# SCH_Final_Syntheseproject_Oliver_2023-12.net
KiCad netlist of a schematic drawn in EasyEDA
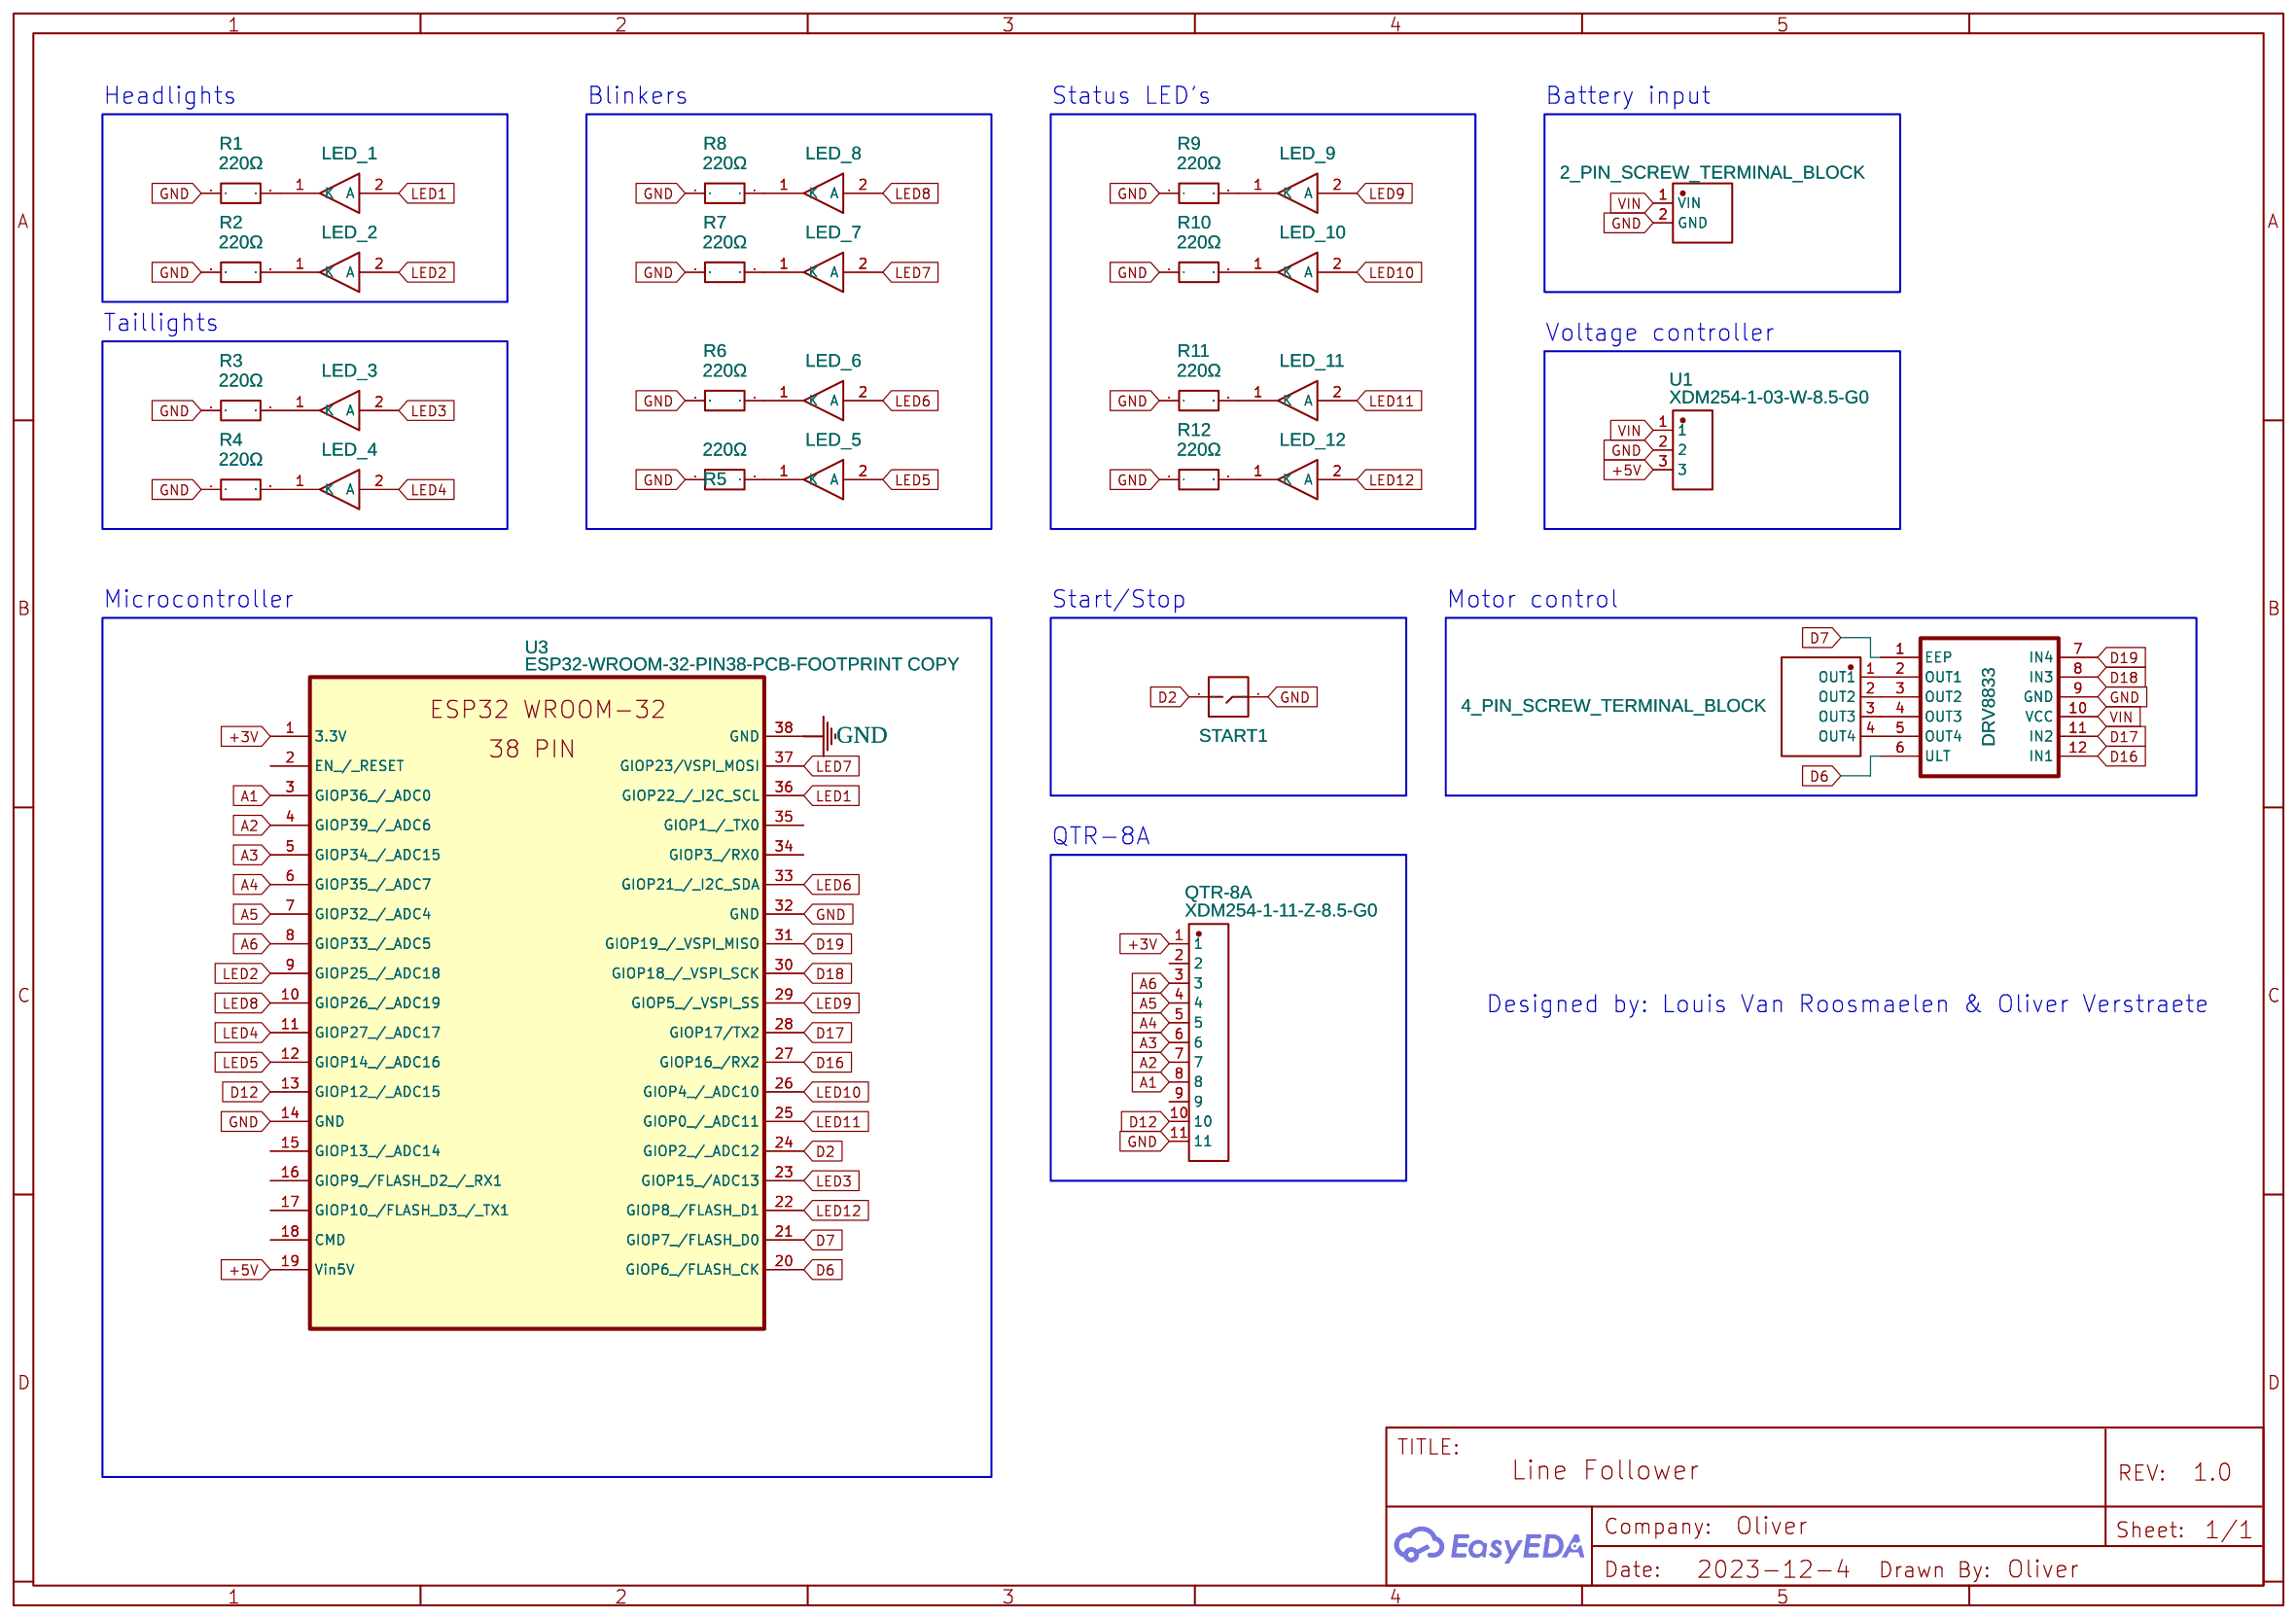
[diagram p0: schematic sheet]

(export (version "E")
  (design (tool "Eeschema 10.0.6"))
  (components
    (comp (ref "2_PIN_SCREW_TERMINAL_BLOCK")
      (value "2 Pin Screw Terminal Block Connector 2.54 mm")
      (libsource (lib "") (part "2 PIN SCREW TERMINAL BLOCK CONNECTOR 2.54 MM"))
    )
    (comp (ref "4_PIN_SCREW_TERMINAL_BLOCK")
      (value "4 PIN SCREW TERMINAL BLOCK CONNECTOR 2.54 MM")
      (libsource (lib "") (part "4 PIN SCREW TERMINAL BLOCK CONNECTOR 2.54 MM"))
    )
    (comp (ref "DRV8833") (value "DRV8833") (libsource (lib "") (part "DRV8833 12PIN")))
    (comp (ref "LED_1") (value "led 5 mm") (libsource (lib "") (part "led 5 mm")))
    (comp (ref "LED_2") (value "led 5 mm") (libsource (lib "") (part "led 5 mm")))
    (comp (ref "LED_3") (value "led 5 mm") (libsource (lib "") (part "led 5 mm")))
    (comp (ref "LED_4") (value "led 5 mm") (libsource (lib "") (part "led 5 mm")))
    (comp (ref "LED_5") (value "led 5 mm") (libsource (lib "") (part "led 5 mm")))
    (comp (ref "LED_6") (value "led 5 mm") (libsource (lib "") (part "led 5 mm")))
    (comp (ref "LED_7") (value "led 5 mm") (libsource (lib "") (part "led 5 mm")))
    (comp (ref "LED_8") (value "led 5 mm") (libsource (lib "") (part "led 5 mm")))
    (comp (ref "LED_9") (value "led 5 mm") (libsource (lib "") (part "led 5 mm")))
    (comp (ref "LED_10") (value "led 5 mm") (libsource (lib "") (part "led 5 mm")))
    (comp (ref "LED_11") (value "led 5 mm") (libsource (lib "") (part "led 5 mm")))
    (comp (ref "LED_12") (value "led 5 mm") (libsource (lib "") (part "led 5 mm")))
    (comp (ref "QTR-8A")
      (value "XDM254-1-11-Z-8.5-G0")
      (fields (field (name "Manufacturer") "XUNDA(讯答)"))
      (libsource (lib "") (part "XDM254-1-11-Z-8.5-G0"))
    )
    (comp (ref "R1")
      (value "220Ω")
      (libsource (lib "") (part "AXIAL RESISTOR 220 OHM - TH_BD2.3-L6.0-P10.00-D0.4"))
    )
    (comp (ref "R2")
      (value "220Ω")
      (libsource (lib "") (part "AXIAL RESISTOR 220 OHM - TH_BD2.3-L6.0-P10.00-D0.4"))
    )
    (comp (ref "R3")
      (value "220Ω")
      (libsource (lib "") (part "AXIAL RESISTOR 220 OHM - TH_BD2.3-L6.0-P10.00-D0.4"))
    )
    (comp (ref "R4")
      (value "220Ω")
      (libsource (lib "") (part "AXIAL RESISTOR 220 OHM - TH_BD2.3-L6.0-P10.00-D0.4"))
    )
    (comp (ref "R5")
      (value "220Ω")
      (libsource (lib "") (part "AXIAL RESISTOR 220 OHM - TH_BD2.3-L6.0-P10.00-D0.4"))
    )
    (comp (ref "R6")
      (value "220Ω")
      (libsource (lib "") (part "AXIAL RESISTOR 220 OHM - TH_BD2.3-L6.0-P10.00-D0.4"))
    )
    (comp (ref "R7")
      (value "220Ω")
      (libsource (lib "") (part "AXIAL RESISTOR 220 OHM - TH_BD2.3-L6.0-P10.00-D0.4"))
    )
    (comp (ref "R8")
      (value "220Ω")
      (libsource (lib "") (part "AXIAL RESISTOR 220 OHM - TH_BD2.3-L6.0-P10.00-D0.4"))
    )
    (comp (ref "R9")
      (value "220Ω")
      (libsource (lib "") (part "AXIAL RESISTOR 220 OHM - TH_BD2.3-L6.0-P10.00-D0.4"))
    )
    (comp (ref "R10")
      (value "220Ω")
      (libsource (lib "") (part "AXIAL RESISTOR 220 OHM - TH_BD2.3-L6.0-P10.00-D0.4"))
    )
    (comp (ref "R11")
      (value "220Ω")
      (libsource (lib "") (part "AXIAL RESISTOR 220 OHM - TH_BD2.3-L6.0-P10.00-D0.4"))
    )
    (comp (ref "R12")
      (value "220Ω")
      (libsource (lib "") (part "AXIAL RESISTOR 220 OHM - TH_BD2.3-L6.0-P10.00-D0.4"))
    )
    (comp (ref "START1") (value "start") (libsource (lib "") (part "Push Button")))
    (comp (ref "U1")
      (value "XDM254-1-03-W-8.5-G0")
      (fields (field (name "Manufacturer") "XUNDA(讯答)"))
      (libsource (lib "") (part "XDM254-1-03-W-8.5-G0"))
    )
    (comp (ref "U3")
      (value "ESP32-WROOM-32-PIN38-PCB-FOOTPRINT COPY")
      (fields
        (field (name "Manufacturer Part") "ESP32-WROOM-32")
        (field (name "Manufacturer") "Espressif Systems")
      )
      (libsource (lib "") (part "ESP32-WROOM-32-PIN38-PCB-FOOTPRINT COPY"))
    )
  )
  (nets
    (net (code "1") (name "+3V") (class "Default")
      (node (ref "QTR-8A") (pin "1") (pinfunction "1_1") (pintype "unspecified"))
      (node (ref "U3") (pin "1") (pinfunction "3.3V_1") (pintype "unspecified"))
    )
    (net (code "2") (name "+5V") (class "Default")
      (node (ref "U1") (pin "3") (pinfunction "3_3") (pintype "unspecified"))
      (node (ref "U3") (pin "19") (pinfunction "Vin5V_19") (pintype "unspecified"))
    )
    (net (code "3") (name "A1") (class "Default")
      (node (ref "QTR-8A") (pin "8") (pinfunction "8_8") (pintype "unspecified"))
      (node (ref "U3") (pin "3") (pinfunction "GIOP36_/_ADC0_3") (pintype "unspecified"))
    )
    (net (code "4") (name "A2") (class "Default")
      (node (ref "QTR-8A") (pin "7") (pinfunction "7_7") (pintype "unspecified"))
      (node (ref "U3") (pin "4") (pinfunction "GIOP39_/_ADC6_4") (pintype "unspecified"))
    )
    (net (code "5") (name "A3") (class "Default")
      (node (ref "QTR-8A") (pin "6") (pinfunction "6_6") (pintype "unspecified"))
      (node (ref "U3") (pin "5") (pinfunction "GIOP34_/_ADC15_5") (pintype "unspecified"))
    )
    (net (code "6") (name "A4") (class "Default")
      (node (ref "QTR-8A") (pin "5") (pinfunction "5_5") (pintype "unspecified"))
      (node (ref "U3") (pin "6") (pinfunction "GIOP35_/_ADC7_6") (pintype "unspecified"))
    )
    (net (code "7") (name "A5") (class "Default")
      (node (ref "QTR-8A") (pin "4") (pinfunction "4_4") (pintype "unspecified"))
      (node (ref "U3") (pin "7") (pinfunction "GIOP32_/_ADC4_7") (pintype "unspecified"))
    )
    (net (code "8") (name "A6") (class "Default")
      (node (ref "QTR-8A") (pin "3") (pinfunction "3_3") (pintype "unspecified"))
      (node (ref "U3") (pin "8") (pinfunction "GIOP33_/_ADC5_8") (pintype "unspecified"))
    )
    (net (code "9") (name "D2") (class "Default")
      (node (ref "START1") (pin "1") (pinfunction "1_1") (pintype "unspecified"))
      (node (ref "U3") (pin "24") (pinfunction "GIOP2_/_ADC12_24") (pintype "unspecified"))
    )
    (net (code "10") (name "D6") (class "Default")
      (node (ref "DRV8833") (pin "6") (pinfunction "ULT_6") (pintype "unspecified"))
      (node (ref "U3") (pin "20") (pinfunction "GIOP6_/FLASH_CK_20") (pintype "unspecified"))
    )
    (net (code "11") (name "D7") (class "Default")
      (node (ref "DRV8833") (pin "1") (pinfunction "EEP_1") (pintype "unspecified"))
      (node (ref "U3") (pin "21") (pinfunction "GIOP7_/FLASH_D0_21") (pintype "unspecified"))
    )
    (net (code "12") (name "D12") (class "Default")
      (node (ref "QTR-8A") (pin "10") (pinfunction "10_10") (pintype "unspecified"))
      (node (ref "U3") (pin "13") (pinfunction "GIOP12_/_ADC15_13") (pintype "unspecified"))
    )
    (net (code "13") (name "D16") (class "Default")
      (node (ref "DRV8833") (pin "12") (pinfunction "IN1_12") (pintype "unspecified"))
      (node (ref "U3") (pin "27") (pinfunction "GIOP16_/RX2_27") (pintype "unspecified"))
    )
    (net (code "14") (name "D17") (class "Default")
      (node (ref "DRV8833") (pin "11") (pinfunction "IN2_11") (pintype "unspecified"))
      (node (ref "U3") (pin "28") (pinfunction "GIOP17/TX2_28") (pintype "unspecified"))
    )
    (net (code "15") (name "D18") (class "Default")
      (node (ref "DRV8833") (pin "8") (pinfunction "IN3_8") (pintype "unspecified"))
      (node (ref "U3") (pin "30") (pinfunction "GIOP18_/_VSPI_SCK_30") (pintype "unspecified"))
    )
    (net (code "16") (name "D19") (class "Default")
      (node (ref "DRV8833") (pin "7") (pinfunction "IN4_7") (pintype "unspecified"))
      (node (ref "U3") (pin "31") (pinfunction "GIOP19_/_VSPI_MISO_31") (pintype "unspecified"))
    )
    (net (code "17") (name "GND") (class "Default")
      (node (ref "2_PIN_SCREW_TERMINAL_BLOCK") (pin "2") (pinfunction "GND_2") (pintype "unspecified"))
      (node (ref "DRV8833") (pin "9") (pinfunction "GND_9") (pintype "unspecified"))
      (node (ref "QTR-8A") (pin "11") (pinfunction "11_11") (pintype "unspecified"))
      (node (ref "R1") (pin "1") (pinfunction "1_1") (pintype "unspecified"))
      (node (ref "R10") (pin "1") (pinfunction "1_1") (pintype "unspecified"))
      (node (ref "R11") (pin "1") (pinfunction "1_1") (pintype "unspecified"))
      (node (ref "R12") (pin "1") (pinfunction "1_1") (pintype "unspecified"))
      (node (ref "R2") (pin "1") (pinfunction "1_1") (pintype "unspecified"))
      (node (ref "R3") (pin "1") (pinfunction "1_1") (pintype "unspecified"))
      (node (ref "R4") (pin "1") (pinfunction "1_1") (pintype "unspecified"))
      (node (ref "R5") (pin "1") (pinfunction "1_1") (pintype "unspecified"))
      (node (ref "R6") (pin "1") (pinfunction "1_1") (pintype "unspecified"))
      (node (ref "R7") (pin "1") (pinfunction "1_1") (pintype "unspecified"))
      (node (ref "R8") (pin "1") (pinfunction "1_1") (pintype "unspecified"))
      (node (ref "R9") (pin "1") (pinfunction "1_1") (pintype "unspecified"))
      (node (ref "START1") (pin "2") (pinfunction "2_2") (pintype "unspecified"))
      (node (ref "U1") (pin "2") (pinfunction "2_2") (pintype "unspecified"))
      (node (ref "U3") (pin "14") (pinfunction "GND_14") (pintype "unspecified"))
      (node (ref "U3") (pin "32") (pinfunction "GND_32") (pintype "unspecified"))
      (node (ref "U3") (pin "38") (pinfunction "GND_38") (pintype "unspecified"))
    )
    (net (code "18") (name "LED1") (class "Default")
      (node (ref "LED_1") (pin "2") (pinfunction "A_2") (pintype "unspecified"))
      (node (ref "U3") (pin "36") (pinfunction "GIOP22_/_I2C_SCL_36") (pintype "unspecified"))
    )
    (net (code "19") (name "LED2") (class "Default")
      (node (ref "LED_2") (pin "2") (pinfunction "A_2") (pintype "unspecified"))
      (node (ref "U3") (pin "9") (pinfunction "GIOP25_/_ADC18_9") (pintype "unspecified"))
    )
    (net (code "20") (name "LED3") (class "Default")
      (node (ref "LED_3") (pin "2") (pinfunction "A_2") (pintype "unspecified"))
      (node (ref "U3") (pin "23") (pinfunction "GIOP15_/ADC13_23") (pintype "unspecified"))
    )
    (net (code "21") (name "LED4") (class "Default")
      (node (ref "LED_4") (pin "2") (pinfunction "A_2") (pintype "unspecified"))
      (node (ref "U3") (pin "11") (pinfunction "GIOP27_/_ADC17_11") (pintype "unspecified"))
    )
    (net (code "22") (name "LED5") (class "Default")
      (node (ref "LED_5") (pin "2") (pinfunction "A_2") (pintype "unspecified"))
      (node (ref "U3") (pin "12") (pinfunction "GIOP14_/_ADC16_12") (pintype "unspecified"))
    )
    (net (code "23") (name "LED6") (class "Default")
      (node (ref "LED_6") (pin "2") (pinfunction "A_2") (pintype "unspecified"))
      (node (ref "U3") (pin "33") (pinfunction "GIOP21_/_I2C_SDA_33") (pintype "unspecified"))
    )
    (net (code "24") (name "LED7") (class "Default")
      (node (ref "LED_7") (pin "2") (pinfunction "A_2") (pintype "unspecified"))
      (node (ref "U3") (pin "37") (pinfunction "GIOP23/VSPI_MOSI_37") (pintype "unspecified"))
    )
    (net (code "25") (name "LED8") (class "Default")
      (node (ref "LED_8") (pin "2") (pinfunction "A_2") (pintype "unspecified"))
      (node (ref "U3") (pin "10") (pinfunction "GIOP26_/_ADC19_10") (pintype "unspecified"))
    )
    (net (code "26") (name "LED9") (class "Default")
      (node (ref "LED_9") (pin "2") (pinfunction "A_2") (pintype "unspecified"))
      (node (ref "U3") (pin "29") (pinfunction "GIOP5_/_VSPI_SS_29") (pintype "unspecified"))
    )
    (net (code "27") (name "LED10") (class "Default")
      (node (ref "LED_10") (pin "2") (pinfunction "A_2") (pintype "unspecified"))
      (node (ref "U3") (pin "26") (pinfunction "GIOP4_/_ADC10_26") (pintype "unspecified"))
    )
    (net (code "28") (name "LED11") (class "Default")
      (node (ref "LED_11") (pin "2") (pinfunction "A_2") (pintype "unspecified"))
      (node (ref "U3") (pin "25") (pinfunction "GIOP0_/_ADC11_25") (pintype "unspecified"))
    )
    (net (code "29") (name "LED12") (class "Default")
      (node (ref "LED_12") (pin "2") (pinfunction "A_2") (pintype "unspecified"))
      (node (ref "U3") (pin "22") (pinfunction "GIOP8_/FLASH_D1_22") (pintype "unspecified"))
    )
    (net (code "30") (name "Net-(4_PIN_SCREW_TERMINAL_BLOCK-OUT1)") (class "Default")
      (node (ref "4_PIN_SCREW_TERMINAL_BLOCK") (pin "1") (pinfunction "OUT1_1") (pintype "unspecified"))
      (node (ref "DRV8833") (pin "2") (pinfunction "OUT1_2") (pintype "unspecified"))
    )
    (net (code "31") (name "Net-(4_PIN_SCREW_TERMINAL_BLOCK-OUT2)") (class "Default")
      (node (ref "4_PIN_SCREW_TERMINAL_BLOCK") (pin "2") (pinfunction "OUT2_2") (pintype "unspecified"))
      (node (ref "DRV8833") (pin "3") (pinfunction "OUT2_3") (pintype "unspecified"))
    )
    (net (code "32") (name "Net-(4_PIN_SCREW_TERMINAL_BLOCK-OUT3)") (class "Default")
      (node (ref "4_PIN_SCREW_TERMINAL_BLOCK") (pin "3") (pinfunction "OUT3_3") (pintype "unspecified"))
      (node (ref "DRV8833") (pin "4") (pinfunction "OUT3_4") (pintype "unspecified"))
    )
    (net (code "33") (name "Net-(4_PIN_SCREW_TERMINAL_BLOCK-OUT4)") (class "Default")
      (node (ref "4_PIN_SCREW_TERMINAL_BLOCK") (pin "4") (pinfunction "OUT4_4") (pintype "unspecified"))
      (node (ref "DRV8833") (pin "5") (pinfunction "OUT4_5") (pintype "unspecified"))
    )
    (net (code "34") (name "Net-(LED_1-K)") (class "Default")
      (node (ref "LED_1") (pin "1") (pinfunction "K_1") (pintype "unspecified"))
      (node (ref "R1") (pin "2") (pinfunction "2_2") (pintype "unspecified"))
    )
    (net (code "35") (name "Net-(LED_2-K)") (class "Default")
      (node (ref "LED_2") (pin "1") (pinfunction "K_1") (pintype "unspecified"))
      (node (ref "R2") (pin "2") (pinfunction "2_2") (pintype "unspecified"))
    )
    (net (code "36") (name "Net-(LED_3-K)") (class "Default")
      (node (ref "LED_3") (pin "1") (pinfunction "K_1") (pintype "unspecified"))
      (node (ref "R3") (pin "2") (pinfunction "2_2") (pintype "unspecified"))
    )
    (net (code "37") (name "Net-(LED_4-K)") (class "Default")
      (node (ref "LED_4") (pin "1") (pinfunction "K_1") (pintype "unspecified"))
      (node (ref "R4") (pin "2") (pinfunction "2_2") (pintype "unspecified"))
    )
    (net (code "38") (name "Net-(LED_5-K)") (class "Default")
      (node (ref "LED_5") (pin "1") (pinfunction "K_1") (pintype "unspecified"))
      (node (ref "R5") (pin "2") (pinfunction "2_2") (pintype "unspecified"))
    )
    (net (code "39") (name "Net-(LED_6-K)") (class "Default")
      (node (ref "LED_6") (pin "1") (pinfunction "K_1") (pintype "unspecified"))
      (node (ref "R6") (pin "2") (pinfunction "2_2") (pintype "unspecified"))
    )
    (net (code "40") (name "Net-(LED_7-K)") (class "Default")
      (node (ref "LED_7") (pin "1") (pinfunction "K_1") (pintype "unspecified"))
      (node (ref "R7") (pin "2") (pinfunction "2_2") (pintype "unspecified"))
    )
    (net (code "41") (name "Net-(LED_8-K)") (class "Default")
      (node (ref "LED_8") (pin "1") (pinfunction "K_1") (pintype "unspecified"))
      (node (ref "R8") (pin "2") (pinfunction "2_2") (pintype "unspecified"))
    )
    (net (code "42") (name "Net-(LED_9-K)") (class "Default")
      (node (ref "LED_9") (pin "1") (pinfunction "K_1") (pintype "unspecified"))
      (node (ref "R9") (pin "2") (pinfunction "2_2") (pintype "unspecified"))
    )
    (net (code "43") (name "Net-(LED_10-K)") (class "Default")
      (node (ref "LED_10") (pin "1") (pinfunction "K_1") (pintype "unspecified"))
      (node (ref "R10") (pin "2") (pinfunction "2_2") (pintype "unspecified"))
    )
    (net (code "44") (name "Net-(LED_11-K)") (class "Default")
      (node (ref "LED_11") (pin "1") (pinfunction "K_1") (pintype "unspecified"))
      (node (ref "R11") (pin "2") (pinfunction "2_2") (pintype "unspecified"))
    )
    (net (code "45") (name "Net-(LED_12-K)") (class "Default")
      (node (ref "LED_12") (pin "1") (pinfunction "K_1") (pintype "unspecified"))
      (node (ref "R12") (pin "2") (pinfunction "2_2") (pintype "unspecified"))
    )
    (net (code "46") (name "VIN") (class "Default")
      (node (ref "2_PIN_SCREW_TERMINAL_BLOCK") (pin "1") (pinfunction "VIN_1") (pintype "unspecified"))
      (node (ref "DRV8833") (pin "10") (pinfunction "VCC_10") (pintype "unspecified"))
      (node (ref "U1") (pin "1") (pinfunction "1_1") (pintype "unspecified"))
    )
    (net (code "47") (name "unconnected-(QTR-8A-Pad2)") (class "Default")
      (node (ref "QTR-8A") (pin "2") (pinfunction "2_2") (pintype "unspecified"))
    )
    (net (code "48") (name "unconnected-(QTR-8A-Pad9)") (class "Default")
      (node (ref "QTR-8A") (pin "9") (pinfunction "9_9") (pintype "unspecified"))
    )
    (net (code "49") (name "unconnected-(U3-CMD-Pad18)") (class "Default")
      (node (ref "U3") (pin "18") (pinfunction "CMD_18") (pintype "unspecified"))
    )
    (net (code "50") (name "unconnected-(U3-EN_{slash}_RESET-Pad2)") (class "Default")
      (node (ref "U3") (pin "2") (pinfunction "EN_/_RESET_2") (pintype "unspecified"))
    )
    (net (code "51") (name "unconnected-(U3-GIOP1_{slash}_TX0-Pad35)") (class "Default")
      (node (ref "U3") (pin "35") (pinfunction "GIOP1_/_TX0_35") (pintype "unspecified"))
    )
    (net (code "52") (name "unconnected-(U3-GIOP3_{slash}RX0-Pad34)") (class "Default")
      (node (ref "U3") (pin "34") (pinfunction "GIOP3_/RX0_34") (pintype "unspecified"))
    )
    (net (code "53") (name "unconnected-(U3-GIOP9_{slash}FLASH_D2_{slash}_RX1-Pad16)") (class "Default")
      (node (ref "U3") (pin "16") (pinfunction "GIOP9_/FLASH_D2_/_RX1_16") (pintype "unspecified"))
    )
    (net (code "54") (name "unconnected-(U3-GIOP10_{slash}FLASH_D3_{slash}_TX1-Pad17)") (class "Default")
      (node (ref "U3") (pin "17") (pinfunction "GIOP10_/FLASH_D3_/_TX1_17") (pintype "unspecified"))
    )
    (net (code "55") (name "unconnected-(U3-GIOP13_{slash}_ADC14-Pad15)") (class "Default")
      (node (ref "U3") (pin "15") (pinfunction "GIOP13_/_ADC14_15") (pintype "unspecified"))
    )
  )
)
